# openSX70-dongle_SEEED_v52.net
KiCad netlist of a schematic drawn in EAGLE
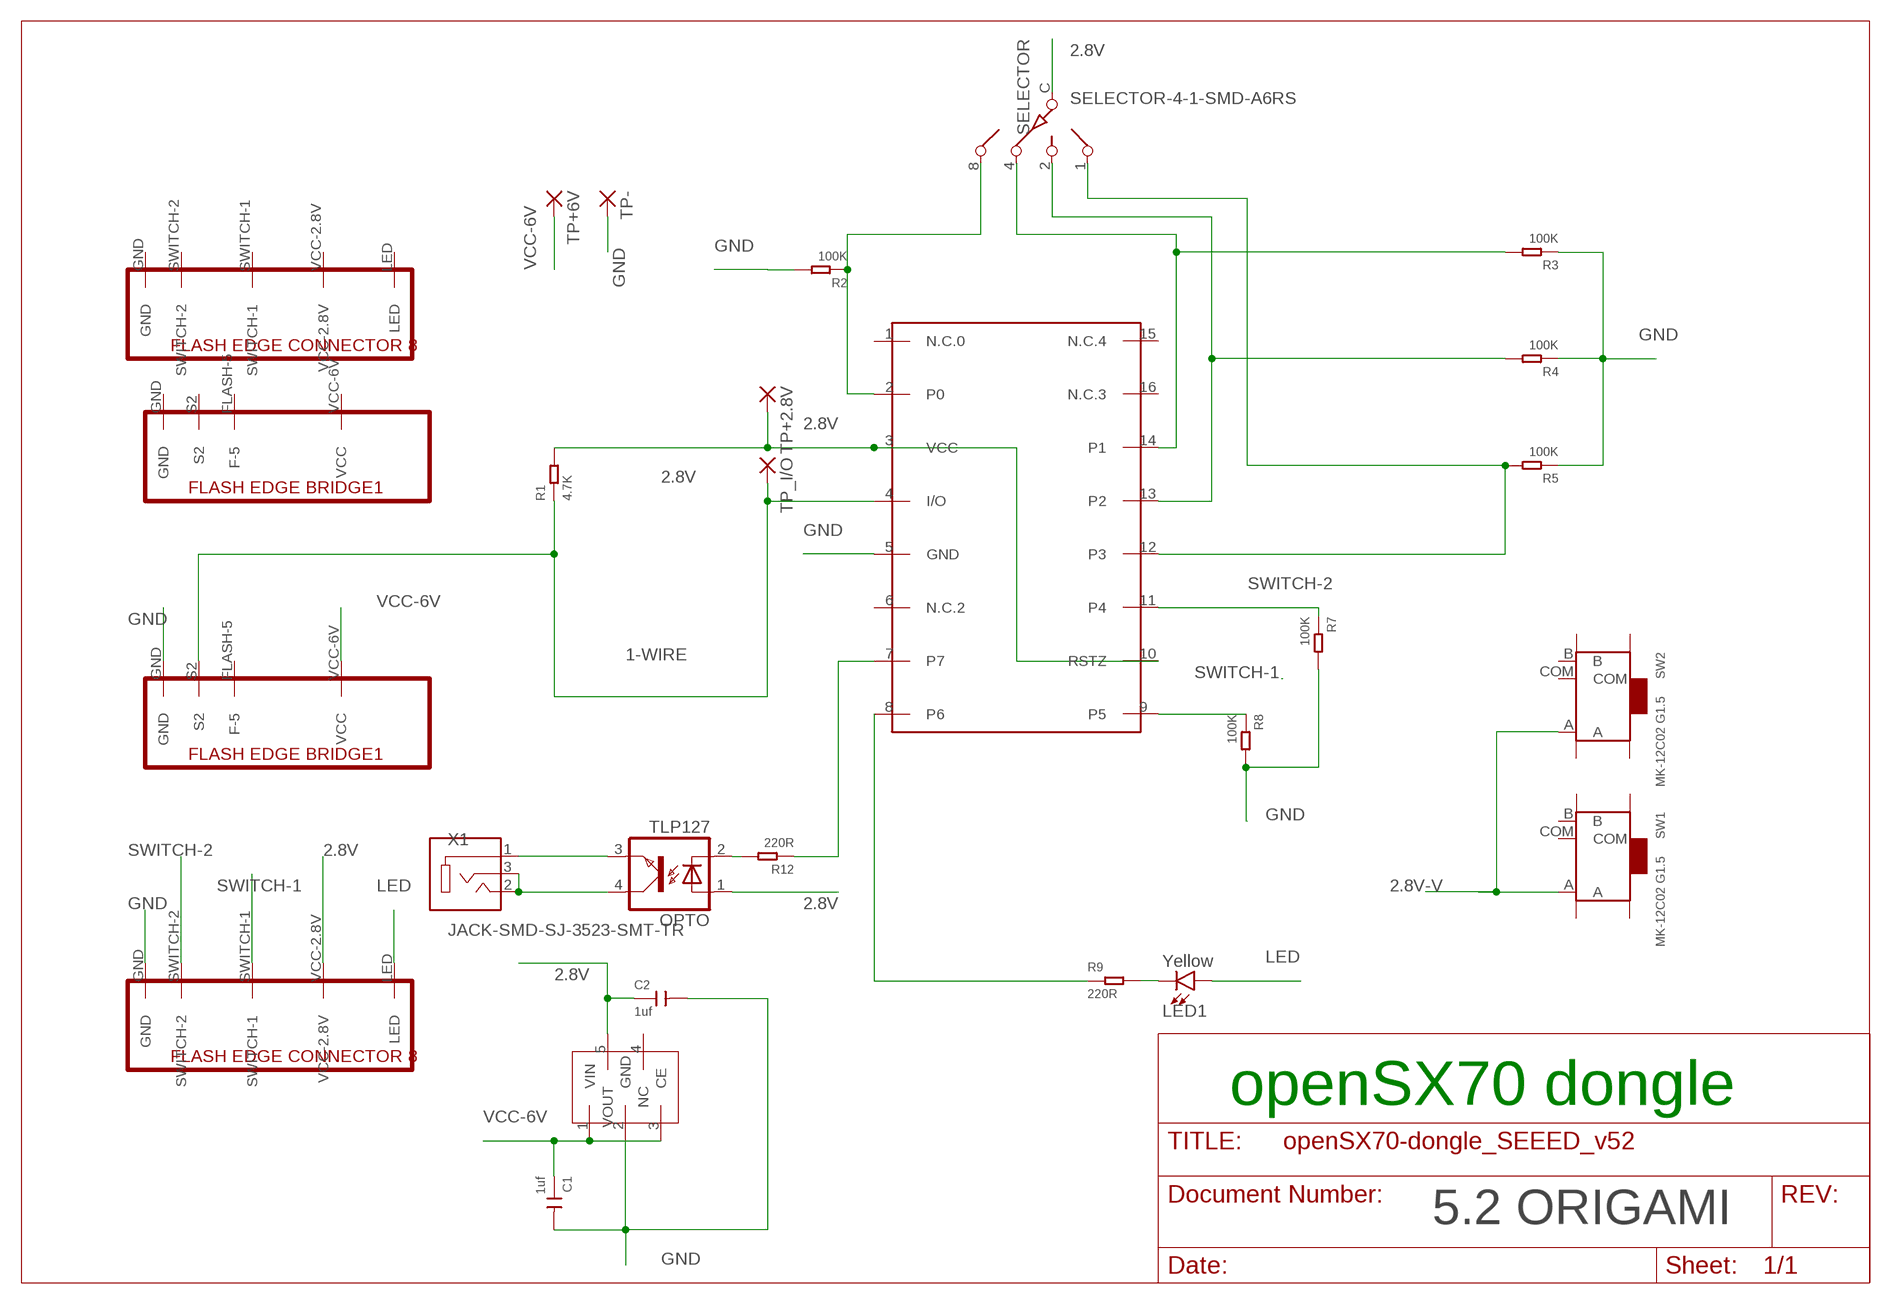
[diagram p0: schematic, sheet 1]

(export (version "E")
  (design (tool "Eeschema 10.0.6"))
  (components
    (comp (ref "C1")
      (value "1uf")
      (footprint "eagle-import:C0603")
      (fields (field (name "MPN") "CC0603KRX7R8BB105"))
      (libsource (lib "eagle-import") (part "CERAMIC-1UF-25V-10%-X7R(0603)"))
    )
    (comp (ref "C2")
      (value "1uf")
      (footprint "eagle-import:C0603")
      (fields (field (name "MPN") "CC0603KRX7R8BB105"))
      (libsource (lib "eagle-import") (part "CERAMIC-1UF-25V-10%-X7R(0603)"))
    )
    (comp (ref "DS2408")
      (value "DS2408")
      (footprint "eagle-import:SO16")
      (libsource (lib "eagle-import") (part "DS2408"))
    )
    (comp (ref "LED1")
      (value "Yellow")
      (footprint "eagle-import:LED-1206")
      (libsource (lib "eagle-import") (part "LED-YELLOWLILYPAD"))
    )
    (comp (ref "OPTO")
      (value "TLP127")
      (footprint "eagle-import:SO-4")
      (libsource (lib "eagle-import") (part "TLP127"))
    )
    (comp (ref "R1")
      (value "4.7K")
      (footprint "eagle-import:R0603")
      (fields (field (name "MPN") "RC0603JR-074K7L"))
      (libsource (lib "eagle-import") (part "SMD-RES-4.7K-5%-1/10W(0603)"))
    )
    (comp (ref "R2")
      (value "100K")
      (footprint "eagle-import:R0603")
      (fields (field (name "MPN") "RC0603FR-07100KL"))
      (libsource (lib "eagle-import") (part "SMD-RES-100K-1%-1/10W(0603)"))
    )
    (comp (ref "R3")
      (value "100K")
      (footprint "eagle-import:R0603")
      (fields (field (name "MPN") "RC0603FR-07100KL"))
      (libsource (lib "eagle-import") (part "SMD-RES-100K-1%-1/10W(0603)"))
    )
    (comp (ref "R4")
      (value "100K")
      (footprint "eagle-import:R0603")
      (fields (field (name "MPN") "RC0603FR-07100KL"))
      (libsource (lib "eagle-import") (part "SMD-RES-100K-1%-1/10W(0603)"))
    )
    (comp (ref "R5")
      (value "100K")
      (footprint "eagle-import:R0603")
      (fields (field (name "MPN") "RC0603FR-07100KL"))
      (libsource (lib "eagle-import") (part "SMD-RES-100K-1%-1/10W(0603)"))
    )
    (comp (ref "R7")
      (value "100K")
      (footprint "eagle-import:R0603")
      (fields (field (name "MPN") "RC0603FR-07100KL"))
      (libsource (lib "eagle-import") (part "SMD-RES-100K-1%-1/10W(0603)"))
    )
    (comp (ref "R8")
      (value "100K")
      (footprint "eagle-import:R0603")
      (fields (field (name "MPN") "RC0603FR-07100KL"))
      (libsource (lib "eagle-import") (part "SMD-RES-100K-1%-1/10W(0603)"))
    )
    (comp (ref "R9")
      (value "220R")
      (footprint "eagle-import:R0603")
      (fields (field (name "MPN") "RC0603JR-07220RL"))
      (libsource (lib "eagle-import") (part "SMD-RES-220R-5%-1/10W(0603)"))
    )
    (comp (ref "R12")
      (value "220R")
      (footprint "eagle-import:R0603")
      (fields (field (name "MPN") "RC0603JR-07220RL"))
      (libsource (lib "eagle-import") (part "SMD-RES-220R-5%-1/10W(0603)"))
    )
    (comp (ref "REG")
      (value "NCP4688")
      (footprint "eagle-import:SOT-23-5")
      (libsource (lib "eagle-import") (part "NCP4688"))
    )
    (comp (ref "SELECTOR")
      (value "SELECTOR-4-1-SMD-A6RS")
      (footprint "eagle-import:A6RS-161RS")
      (libsource (lib "eagle-import") (part "SELECTOR-4-1-SMD-A6RS"))
    )
    (comp (ref "SW1")
      (value "MK-12C02 G1.5")
      (footprint "eagle-import:SW7-SMD-L6.7X2.7X3.2MM")
      (libsource (lib "eagle-import") (part "SMD-TOGGLE-SWITCH-ON-ON(3+4P-6.7X2.7MM)"))
    )
    (comp (ref "SW2")
      (value "MK-12C02 G1.5")
      (footprint "eagle-import:SW7-SMD-L6.7X2.7X3.2MM")
      (libsource (lib "eagle-import") (part "SMD-TOGGLE-SWITCH-ON-ON(3+4P-6.7X2.7MM)"))
    )
    (comp (ref "TP+2.8V")
      (value "SMD2")
      (footprint "eagle-import:SMD1,27-2,54")
      (libsource (lib "eagle-import") (part "SMD2"))
    )
    (comp (ref "TP+6V")
      (value "SMD2")
      (footprint "eagle-import:SMD1,27-2,54")
      (libsource (lib "eagle-import") (part "SMD2"))
    )
    (comp (ref "TP-")
      (value "SMD2")
      (footprint "eagle-import:SMD1,27-2,54")
      (libsource (lib "eagle-import") (part "SMD2"))
    )
    (comp (ref "TP_I/O")
      (value "SMD2")
      (footprint "eagle-import:SMD1,27-2,54")
      (libsource (lib "eagle-import") (part "SMD2"))
    )
    (comp (ref "U$1")
      (value "FLASH-BRIDGE-SW1-SW2-LED-SMALL")
      (footprint "eagle-import:FLASH-8-BRIDGE-SW1-SW2-LED-SMALL")
      (libsource (lib "eagle-import") (part "FLASH-BRIDGE-SW1-SW2-LED-SMALL"))
    )
    (comp (ref "U$2")
      (value "FLASH-BRIDGE1")
      (footprint "eagle-import:FLASH-8-BRIDGE1")
      (libsource (lib "eagle-import") (part "FLASH-BRIDGE1"))
    )
    (comp (ref "U$3")
      (value "FLASH-BRIDGE-SW1-SW2-LED")
      (footprint "eagle-import:FLASH-8-BRIDGE-SW1-SW2-LED")
      (libsource (lib "eagle-import") (part "FLASH-BRIDGE-SW1-SW2-LED"))
    )
    (comp (ref "U$4")
      (value "FLASH-BRIDGE-SMALL")
      (footprint "eagle-import:FLASH-8-BRIDGE1-SMALL")
      (libsource (lib "eagle-import") (part "FLASH-BRIDGE-SMALL"))
    )
    (comp (ref "X1")
      (value "JACK-SMD-SJ-3523-SMT-TR")
      (footprint "eagle-import:CUI_SJ-3523-SMT-TR")
      (fields (field (name "MF") "CUI Inc.") (field (name "MP") "SJ-3523-SMT-TR"))
      (libsource (lib "eagle-import") (part "JACK-SMD-SJ-3523-SMT-TR"))
    )
  )
  (nets
    (net (code "1") (name "/1-WIRE") (class "Default")
      (node (ref "DS2408") (pin "4") (pinfunction "I/O_4") (pintype "bidirectional"))
      (node (ref "R1") (pin "1") (pinfunction "1_1") (pintype "passive"))
      (node (ref "TP_I/O") (pin "1") (pinfunction "P_1") (pintype "passive"))
      (node (ref "U$2") (pin "S2") (pinfunction "S2_S2") (pintype "bidirectional"))
    )
    (net (code "2") (name "/2.8V") (class "Default")
      (node (ref "C2") (pin "1") (pinfunction "1_1") (pintype "passive"))
      (node (ref "DS2408") (pin "10") (pinfunction "RSTZ_10") (pintype "bidirectional"))
      (node (ref "DS2408") (pin "3") (pinfunction "VCC_3") (pintype "bidirectional"))
      (node (ref "OPTO") (pin "1") (pinfunction "A_1") (pintype "passive"))
      (node (ref "R1") (pin "2") (pinfunction "2_2") (pintype "passive"))
      (node (ref "REG") (pin "5") (pinfunction "VOUT_5") (pintype "bidirectional"))
      (node (ref "SELECTOR") (pin "C") (pinfunction "C_C") (pintype "passive"))
      (node (ref "TP+2.8V") (pin "1") (pinfunction "P_1") (pintype "passive"))
      (node (ref "U$3") (pin "VCC-2.8V") (pinfunction "VCC-2.8V_VCC-2.8V") (pintype "bidirectional"))
    )
    (net (code "3") (name "/2.8V-V") (class "Default")
      (node (ref "SW1") (pin "A") (pinfunction "A_A") (pintype "bidirectional"))
      (node (ref "SW2") (pin "A") (pinfunction "A_A") (pintype "bidirectional"))
    )
    (net (code "4") (name "/GND") (class "Default")
      (node (ref "C1") (pin "2") (pinfunction "2_2") (pintype "passive"))
      (node (ref "C2") (pin "2") (pinfunction "2_2") (pintype "passive"))
      (node (ref "DS2408") (pin "5") (pinfunction "GND_5") (pintype "bidirectional"))
      (node (ref "R2") (pin "2") (pinfunction "2_2") (pintype "passive"))
      (node (ref "R3") (pin "1") (pinfunction "1_1") (pintype "passive"))
      (node (ref "R4") (pin "1") (pinfunction "1_1") (pintype "passive"))
      (node (ref "R5") (pin "1") (pinfunction "1_1") (pintype "passive"))
      (node (ref "R7") (pin "2") (pinfunction "2_2") (pintype "passive"))
      (node (ref "R8") (pin "2") (pinfunction "2_2") (pintype "passive"))
      (node (ref "REG") (pin "2") (pinfunction "GND_2") (pintype "bidirectional"))
      (node (ref "TP-") (pin "1") (pinfunction "P_1") (pintype "passive"))
      (node (ref "U$2") (pin "GND") (pinfunction "GND_GND") (pintype "bidirectional"))
      (node (ref "U$3") (pin "GND") (pinfunction "GND_GND") (pintype "bidirectional"))
    )
    (net (code "5") (name "/LED") (class "Default")
      (node (ref "LED1") (pin "A") (pinfunction "A_A") (pintype "passive"))
      (node (ref "U$3") (pin "LED") (pinfunction "LED_LED") (pintype "bidirectional"))
    )
    (net (code "6") (name "/SWITCH-1") (class "Default")
      (node (ref "DS2408") (pin "9") (pinfunction "P5_9") (pintype "bidirectional"))
      (node (ref "R8") (pin "1") (pinfunction "1_1") (pintype "passive"))
      (node (ref "U$3") (pin "SWITCH-1") (pinfunction "SWITCH-1_SWITCH-1") (pintype "bidirectional"))
    )
    (net (code "7") (name "/SWITCH-2") (class "Default")
      (node (ref "DS2408") (pin "11") (pinfunction "P4_11") (pintype "bidirectional"))
      (node (ref "R7") (pin "1") (pinfunction "1_1") (pintype "passive"))
      (node (ref "U$3") (pin "SWITCH-2") (pinfunction "SWITCH-2_SWITCH-2") (pintype "bidirectional"))
    )
    (net (code "8") (name "/VCC-6V") (class "Default")
      (node (ref "C1") (pin "1") (pinfunction "1_1") (pintype "passive"))
      (node (ref "REG") (pin "1") (pinfunction "VIN_1") (pintype "bidirectional"))
      (node (ref "REG") (pin "3") (pinfunction "CE_3") (pintype "bidirectional"))
      (node (ref "TP+6V") (pin "1") (pinfunction "P_1") (pintype "passive"))
      (node (ref "U$2") (pin "VCC-6V") (pinfunction "VCC_VCC-6V") (pintype "bidirectional"))
    )
    (net (code "9") (name "Net-(DS2408-P0)") (class "Default")
      (node (ref "DS2408") (pin "2") (pinfunction "P0_2") (pintype "bidirectional"))
      (node (ref "R2") (pin "1") (pinfunction "1_1") (pintype "passive"))
      (node (ref "SELECTOR") (pin "8") (pinfunction "8_8") (pintype "passive"))
    )
    (net (code "10") (name "Net-(DS2408-P1)") (class "Default")
      (node (ref "DS2408") (pin "14") (pinfunction "P1_14") (pintype "bidirectional"))
      (node (ref "R3") (pin "2") (pinfunction "2_2") (pintype "passive"))
      (node (ref "SELECTOR") (pin "4") (pinfunction "4_4") (pintype "passive"))
    )
    (net (code "11") (name "Net-(DS2408-P2)") (class "Default")
      (node (ref "DS2408") (pin "13") (pinfunction "P2_13") (pintype "bidirectional"))
      (node (ref "R4") (pin "2") (pinfunction "2_2") (pintype "passive"))
      (node (ref "SELECTOR") (pin "2") (pinfunction "2_2") (pintype "passive"))
    )
    (net (code "12") (name "Net-(DS2408-P3)") (class "Default")
      (node (ref "DS2408") (pin "12") (pinfunction "P3_12") (pintype "bidirectional"))
      (node (ref "R5") (pin "2") (pinfunction "2_2") (pintype "passive"))
      (node (ref "SELECTOR") (pin "1") (pinfunction "1_1") (pintype "passive"))
    )
    (net (code "13") (name "Net-(DS2408-P6)") (class "Default")
      (node (ref "DS2408") (pin "8") (pinfunction "P6_8") (pintype "bidirectional"))
      (node (ref "R9") (pin "1") (pinfunction "1_1") (pintype "passive"))
    )
    (net (code "14") (name "Net-(DS2408-P7)") (class "Default")
      (node (ref "DS2408") (pin "7") (pinfunction "P7_7") (pintype "bidirectional"))
      (node (ref "R12") (pin "1") (pinfunction "1_1") (pintype "passive"))
    )
    (net (code "15") (name "Net-(LED1-PadC)") (class "Default")
      (node (ref "LED1") (pin "C") (pinfunction "C_C") (pintype "passive"))
      (node (ref "R9") (pin "2") (pinfunction "2_2") (pintype "passive"))
    )
    (net (code "16") (name "Net-(OPTO-C)") (class "Default")
      (node (ref "OPTO") (pin "2") (pinfunction "C_2") (pintype "passive"))
      (node (ref "R12") (pin "2") (pinfunction "2_2") (pintype "passive"))
    )
    (net (code "17") (name "Net-(OPTO-COL)") (class "Default")
      (node (ref "OPTO") (pin "4") (pinfunction "COL_4") (pintype "passive"))
      (node (ref "X1") (pin "2") (pinfunction "2_2") (pintype "passive"))
      (node (ref "X1") (pin "3") (pinfunction "3_3") (pintype "passive"))
    )
    (net (code "18") (name "Net-(OPTO-EMIT)") (class "Default")
      (node (ref "OPTO") (pin "3") (pinfunction "EMIT_3") (pintype "passive"))
      (node (ref "X1") (pin "1") (pinfunction "1_1") (pintype "passive"))
    )
    (net (code "19") (name "unconnected-(DS2408-N.C.0-Pad1)") (class "Default")
      (node (ref "DS2408") (pin "1") (pinfunction "N.C.0_1") (pintype "bidirectional"))
    )
    (net (code "20") (name "unconnected-(DS2408-N.C.2-Pad6)") (class "Default")
      (node (ref "DS2408") (pin "6") (pinfunction "N.C.2_6") (pintype "bidirectional"))
    )
    (net (code "21") (name "unconnected-(DS2408-N.C.3-Pad16)") (class "Default")
      (node (ref "DS2408") (pin "16") (pinfunction "N.C.3_16") (pintype "bidirectional"))
    )
    (net (code "22") (name "unconnected-(DS2408-N.C.4-Pad15)") (class "Default")
      (node (ref "DS2408") (pin "15") (pinfunction "N.C.4_15") (pintype "bidirectional"))
    )
    (net (code "23") (name "unconnected-(REG-NC-Pad4)") (class "Default")
      (node (ref "REG") (pin "4") (pinfunction "NC_4") (pintype "bidirectional"))
    )
    (net (code "24") (name "unconnected-(SW1-PadB)") (class "Default")
      (node (ref "SW1") (pin "B") (pinfunction "B_B") (pintype "bidirectional"))
    )
    (net (code "25") (name "unconnected-(SW1-PadCOM)") (class "Default")
      (node (ref "SW1") (pin "COM") (pinfunction "COM_COM") (pintype "bidirectional"))
    )
    (net (code "26") (name "unconnected-(SW1-PadSS1)") (class "Default")
      (node (ref "SW1") (pin "SS1") (pinfunction "SS1_SS1") (pintype "bidirectional"))
    )
    (net (code "27") (name "unconnected-(SW1-PadSS2)") (class "Default")
      (node (ref "SW1") (pin "SS2") (pinfunction "SS2_SS2") (pintype "bidirectional"))
    )
    (net (code "28") (name "unconnected-(SW1-PadSS3)") (class "Default")
      (node (ref "SW1") (pin "SS3") (pinfunction "SS3_SS3") (pintype "bidirectional"))
    )
    (net (code "29") (name "unconnected-(SW1-PadSS4)") (class "Default")
      (node (ref "SW1") (pin "SS4") (pinfunction "SS4_SS4") (pintype "bidirectional"))
    )
    (net (code "30") (name "unconnected-(SW2-PadB)") (class "Default")
      (node (ref "SW2") (pin "B") (pinfunction "B_B") (pintype "bidirectional"))
    )
    (net (code "31") (name "unconnected-(SW2-PadCOM)") (class "Default")
      (node (ref "SW2") (pin "COM") (pinfunction "COM_COM") (pintype "bidirectional"))
    )
    (net (code "32") (name "unconnected-(SW2-PadSS1)") (class "Default")
      (node (ref "SW2") (pin "SS1") (pinfunction "SS1_SS1") (pintype "bidirectional"))
    )
    (net (code "33") (name "unconnected-(SW2-PadSS2)") (class "Default")
      (node (ref "SW2") (pin "SS2") (pinfunction "SS2_SS2") (pintype "bidirectional"))
    )
    (net (code "34") (name "unconnected-(SW2-PadSS3)") (class "Default")
      (node (ref "SW2") (pin "SS3") (pinfunction "SS3_SS3") (pintype "bidirectional"))
    )
    (net (code "35") (name "unconnected-(SW2-PadSS4)") (class "Default")
      (node (ref "SW2") (pin "SS4") (pinfunction "SS4_SS4") (pintype "bidirectional"))
    )
    (net (code "36") (name "unconnected-(U$1-PadGND)") (class "Default")
      (node (ref "U$1") (pin "GND") (pinfunction "GND_GND") (pintype "bidirectional"))
    )
    (net (code "37") (name "unconnected-(U$1-PadLED)") (class "Default")
      (node (ref "U$1") (pin "LED") (pinfunction "LED_LED") (pintype "bidirectional"))
    )
    (net (code "38") (name "unconnected-(U$1-PadSWITCH-1)") (class "Default")
      (node (ref "U$1") (pin "SWITCH-1") (pinfunction "SWITCH-1_SWITCH-1") (pintype "bidirectional"))
    )
    (net (code "39") (name "unconnected-(U$1-PadSWITCH-2)") (class "Default")
      (node (ref "U$1") (pin "SWITCH-2") (pinfunction "SWITCH-2_SWITCH-2") (pintype "bidirectional"))
    )
    (net (code "40") (name "unconnected-(U$1-PadVCC-2.8V)") (class "Default")
      (node (ref "U$1") (pin "VCC-2.8V") (pinfunction "VCC-2.8V_VCC-2.8V") (pintype "bidirectional"))
    )
    (net (code "41") (name "unconnected-(U$2-F-5-PadFLASH-5)") (class "Default")
      (node (ref "U$2") (pin "FLASH-5") (pinfunction "F-5_FLASH-5") (pintype "bidirectional"))
    )
    (net (code "42") (name "unconnected-(U$4-F-5-PadFLASH-5)") (class "Default")
      (node (ref "U$4") (pin "FLASH-5") (pinfunction "F-5_FLASH-5") (pintype "bidirectional"))
    )
    (net (code "43") (name "unconnected-(U$4-PadGND)") (class "Default")
      (node (ref "U$4") (pin "GND") (pinfunction "GND_GND") (pintype "bidirectional"))
    )
    (net (code "44") (name "unconnected-(U$4-PadS2)") (class "Default")
      (node (ref "U$4") (pin "S2") (pinfunction "S2_S2") (pintype "bidirectional"))
    )
    (net (code "45") (name "unconnected-(U$4-VCC-PadVCC-6V)") (class "Default")
      (node (ref "U$4") (pin "VCC-6V") (pinfunction "VCC_VCC-6V") (pintype "bidirectional"))
    )
  )
)
